# Li-ion_charger.net
KiCad netlist of a schematic drawn in Altium Designer
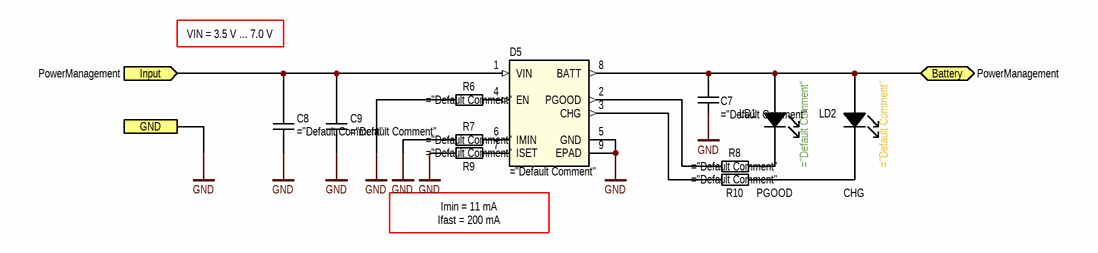
[diagram p0: Li-ion_charger.SchDoc]

(export (version "E")
  (design (tool "Eeschema 10.0.6"))
  (components
    (comp (ref "C7")
      (value "~")
      (description "CAP CER 1UF 10V X5R 0805")
      (fields (field (name "TOLERANCE") "10 %") (field (name "MANUFACTURER") "YAGEO"))
      (libsource (lib "femtoino") (part "CC0805KKX5R6BB105"))
    )
    (comp (ref "C8")
      (value "~")
      (description "CAP CER 10UF 10V X5R 0805")
      (fields (field (name "TOLERANCE") "10 %") (field (name "MANUFACTURER") "YAGEO"))
      (libsource (lib "femtoino") (part "CC0805KPX5R6BB106"))
    )
    (comp (ref "C9")
      (value "~")
      (description "CAP CER 1UF 10V X5R 0805")
      (fields (field (name "TOLERANCE") "10 %") (field (name "MANUFACTURER") "YAGEO"))
      (libsource (lib "femtoino") (part "CC0805KKX5R6BB105"))
    )
    (comp (ref "D5")
      (value "~")
      (description "IC LI-ION BATT CHGR WDFN-8")
      (fields (field (name "TOLERANCE") "* %") (field (name "MANUFACTURER") "Richtek USA Inc."))
      (libsource (lib "femtoino") (part "RT9526AGQW"))
    )
    (comp (ref "LD1")
      (value "~")
      (description "LED GREEN CLEAR SMD")
      (fields (field (name "TOLERANCE") "* %") (field (name "MANUFACTURER") "Lite-On Inc."))
      (libsource (lib "femtoino") (part "LTST-C191KGKT"))
    )
    (comp (ref "LD2")
      (value "~")
      (description "LED YELLOW CLEAR SMD")
      (fields (field (name "TOLERANCE") "* %") (field (name "MANUFACTURER") "Lite-On Inc."))
      (libsource (lib "femtoino") (part "LTST-C191KSKT"))
    )
    (comp (ref "R6")
      (value "~")
      (description "RES 200K OHM 1% 1/10W 0603")
      (fields (field (name "TOLERANCE") "1 %") (field (name "MANUFACTURER") "YAGEO"))
      (libsource (lib "femtoino") (part "RC0603FR-07200KL"))
    )
    (comp (ref "R7")
      (value "~")
      (description "RES 1M OHM 1% 1/10W 0603")
      (fields (field (name "TOLERANCE") "1 %") (field (name "MANUFACTURER") "YAGEO"))
      (libsource (lib "femtoino") (part "RC0603FR-071ML"))
    )
    (comp (ref "R8")
      (value "~")
      (description "RES 270 OHM 1% 1/10W 0603")
      (fields (field (name "TOLERANCE") "1 %") (field (name "MANUFACTURER") "YAGEO"))
      (libsource (lib "femtoino") (part "RC0603FR-07270RL"))
    )
    (comp (ref "R9")
      (value "~")
      (description "RES 62K OHM 1% 1/10W 0603")
      (fields (field (name "TOLERANCE") "1 %") (field (name "MANUFACTURER") "YAGEO"))
      (libsource (lib "femtoino") (part "RC0603FR-0762KL"))
    )
    (comp (ref "R10")
      (value "~")
      (description "RES 270 OHM 1% 1/10W 0603")
      (fields (field (name "TOLERANCE") "1 %") (field (name "MANUFACTURER") "YAGEO"))
      (libsource (lib "femtoino") (part "RC0603FR-07270RL"))
    )
  )
  (nets
    (net (code "1") (name "/Battery") (class "Default")
      (node (ref "C7") (pin "2") (pinfunction "2_2") (pintype "passive"))
      (node (ref "D5") (pin "8") (pinfunction "BATT_8") (pintype "output"))
      (node (ref "LD1") (pin "C") (pinfunction "C_C") (pintype "passive"))
      (node (ref "LD2") (pin "C") (pinfunction "C_C") (pintype "passive"))
    )
    (net (code "2") (name "/Input") (class "Default")
      (node (ref "C8") (pin "1") (pinfunction "1_1") (pintype "passive"))
      (node (ref "C9") (pin "2") (pinfunction "2_2") (pintype "passive"))
      (node (ref "D5") (pin "1") (pinfunction "VIN_1") (pintype "input"))
    )
    (net (code "3") (name "GND") (class "Default")
      (node (ref "C7") (pin "1") (pinfunction "1_1") (pintype "passive"))
      (node (ref "C8") (pin "2") (pinfunction "2_2") (pintype "passive"))
      (node (ref "C9") (pin "1") (pinfunction "1_1") (pintype "passive"))
      (node (ref "D5") (pin "5") (pinfunction "GND_5") (pintype "passive"))
      (node (ref "D5") (pin "9") (pinfunction "EPAD_9") (pintype "passive"))
      (node (ref "R6") (pin "1") (pinfunction "1_1") (pintype "passive"))
      (node (ref "R7") (pin "2") (pinfunction "2_2") (pintype "passive"))
      (node (ref "R9") (pin "1") (pinfunction "1_1") (pintype "passive"))
    )
    (net (code "4") (name "Net-(D5-CHG)") (class "Default")
      (node (ref "D5") (pin "3") (pinfunction "CHG_3") (pintype "output"))
      (node (ref "R10") (pin "1") (pinfunction "1_1") (pintype "passive"))
    )
    (net (code "5") (name "Net-(D5-EN)") (class "Default")
      (node (ref "D5") (pin "4") (pinfunction "EN_4") (pintype "input"))
      (node (ref "R6") (pin "2") (pinfunction "2_2") (pintype "passive"))
    )
    (net (code "6") (name "Net-(D5-IMIN)") (class "Default")
      (node (ref "D5") (pin "6") (pinfunction "IMIN_6") (pintype "passive"))
      (node (ref "R7") (pin "1") (pinfunction "1_1") (pintype "passive"))
    )
    (net (code "7") (name "Net-(D5-ISET)") (class "Default")
      (node (ref "D5") (pin "7") (pinfunction "ISET_7") (pintype "passive"))
      (node (ref "R9") (pin "2") (pinfunction "2_2") (pintype "passive"))
    )
    (net (code "8") (name "Net-(D5-PGOOD)") (class "Default")
      (node (ref "D5") (pin "2") (pinfunction "PGOOD_2") (pintype "output"))
      (node (ref "R8") (pin "1") (pinfunction "1_1") (pintype "passive"))
    )
    (net (code "9") (name "Net-(LD1-PadA)") (class "Default")
      (node (ref "LD1") (pin "A") (pinfunction "A_A") (pintype "passive"))
      (node (ref "R8") (pin "2") (pinfunction "2_2") (pintype "passive"))
    )
    (net (code "10") (name "Net-(LD2-PadA)") (class "Default")
      (node (ref "LD2") (pin "A") (pinfunction "A_A") (pintype "passive"))
      (node (ref "R10") (pin "2") (pinfunction "2_2") (pintype "passive"))
    )
  )
)
